# IMU.net
KiCad netlist of a schematic drawn in Altium Designer
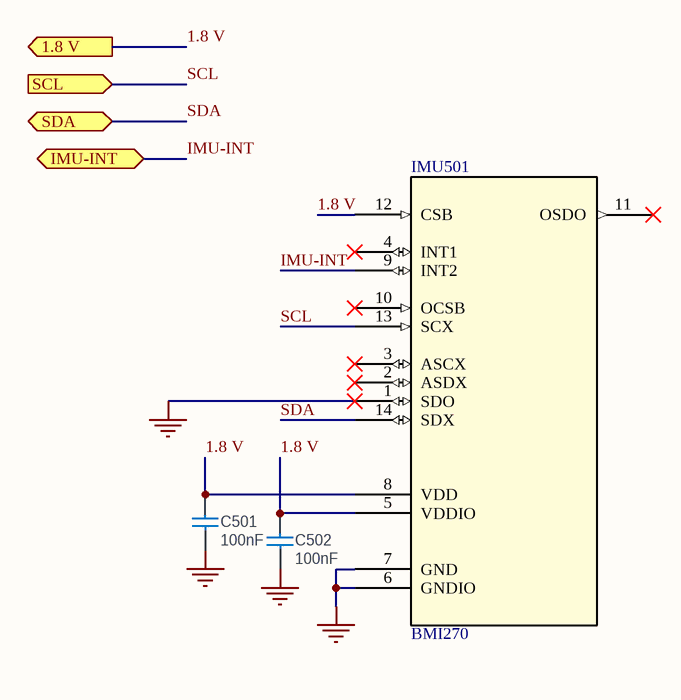
[diagram p0: IMU (BMI270).SchDoc]

(export (version "E")
  (design (tool "Eeschema 10.0.6"))
  (components
    (comp (ref "C501")
      (value "100nF")
      (footprint "CAPC0603X03L_C")
      (description "Capacitor, X7S, ±10%")
      (fields (field (name "AUTHOR") "rsk"))
      (libsource (lib "Watch_Components") (part "C0201-100n-16V-X7S"))
    )
    (comp (ref "C502")
      (value "100nF")
      (footprint "CAPC0603X03L_C")
      (description "Capacitor, X7S, ±10%")
      (fields (field (name "AUTHOR") "rsk"))
      (libsource (lib "Watch_Components") (part "C0201-100n-16V-X7S"))
    )
    (comp (ref "IMU501")
      (value "BMI270")
      (footprint "BMI270_BOS")
      (description "Inertial Measurement Unit Digital Output 1.8V/2.5V/3.3V Automotive 14-Pin LGA")
      (fields (field (name "MANUFACTURER") "Bosch Tools"))
      (libsource (lib "Watch_Components") (part "BMI270"))
    )
  )
  (nets
    (net (code "1") (name "/1.8 V") (class "Default")
      (node (ref "C501") (pin "2") (pinfunction "2_2") (pintype "passive"))
      (node (ref "C502") (pin "2") (pinfunction "2_2") (pintype "passive"))
      (node (ref "IMU501") (pin "12") (pinfunction "CSB_12") (pintype "input"))
      (node (ref "IMU501") (pin "5") (pinfunction "VDDIO_5") (pintype "passive"))
      (node (ref "IMU501") (pin "8") (pinfunction "VDD_8") (pintype "passive"))
    )
    (net (code "2") (name "/IMU-INT") (class "Default")
      (node (ref "IMU501") (pin "9") (pinfunction "INT2_9") (pintype "bidirectional"))
    )
    (net (code "3") (name "/SCL") (class "Default")
      (node (ref "IMU501") (pin "13") (pinfunction "SCX_13") (pintype "input"))
    )
    (net (code "4") (name "/SDA") (class "Default")
      (node (ref "IMU501") (pin "14") (pinfunction "SDX_14") (pintype "bidirectional"))
    )
    (net (code "5") (name "GND") (class "Default")
      (node (ref "C501") (pin "1") (pinfunction "1_1") (pintype "passive"))
      (node (ref "C502") (pin "1") (pinfunction "1_1") (pintype "passive"))
      (node (ref "IMU501") (pin "1") (pinfunction "SDO_1") (pintype "bidirectional"))
      (node (ref "IMU501") (pin "6") (pinfunction "GNDIO_6") (pintype "passive"))
      (node (ref "IMU501") (pin "7") (pinfunction "GND_7") (pintype "passive"))
    )
    (net (code "6") (name "unconnected-(IMU501-ASCX-Pad3)") (class "Default")
      (node (ref "IMU501") (pin "3") (pinfunction "ASCX_3") (pintype "bidirectional+no_connect"))
    )
    (net (code "7") (name "unconnected-(IMU501-ASDX-Pad2)") (class "Default")
      (node (ref "IMU501") (pin "2") (pinfunction "ASDX_2") (pintype "bidirectional+no_connect"))
    )
    (net (code "8") (name "unconnected-(IMU501-INT1-Pad4)") (class "Default")
      (node (ref "IMU501") (pin "4") (pinfunction "INT1_4") (pintype "bidirectional+no_connect"))
    )
    (net (code "9") (name "unconnected-(IMU501-OCSB-Pad10)") (class "Default")
      (node (ref "IMU501") (pin "10") (pinfunction "OCSB_10") (pintype "input+no_connect"))
    )
    (net (code "10") (name "unconnected-(IMU501-OSDO-Pad11)") (class "Default")
      (node (ref "IMU501") (pin "11") (pinfunction "OSDO_11") (pintype "output+no_connect"))
    )
  )
)
